# Power_Supply.net
KiCad netlist of a schematic drawn in Altium Designer
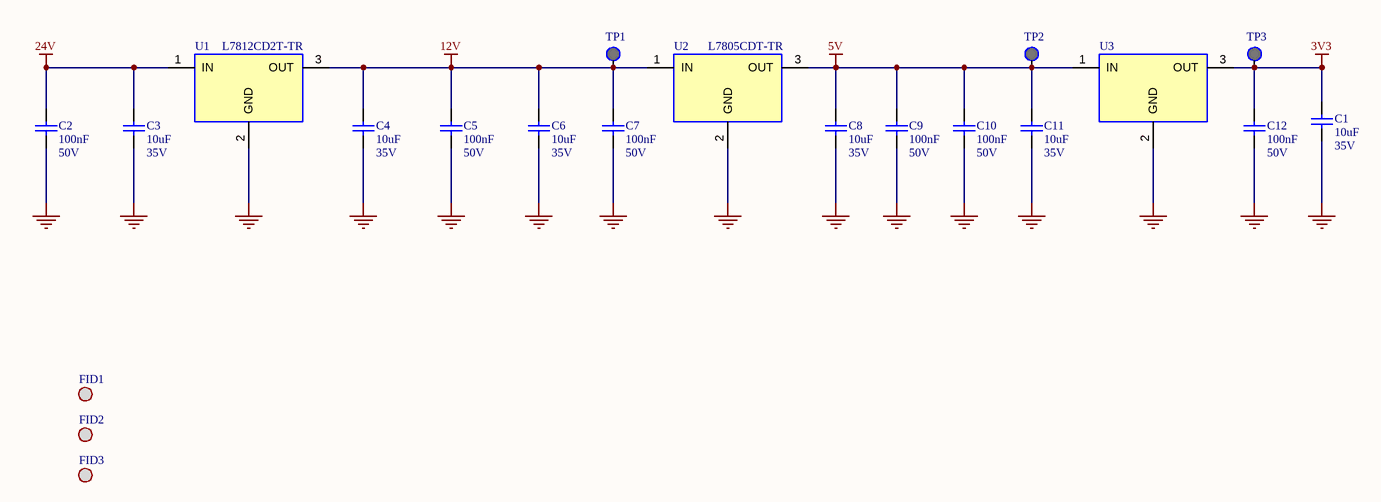
[diagram p0: Power Supply.SchDoc]

(export (version "E")
  (design (tool "Eeschema 10.0.6"))
  (components
    (comp (ref "C1")
      (value "Capacitor")
      (footprint "CAPC1608N")
      (fields
        (field (name "PART NUMBER") "CAP-000000006")
        (field (name "VALUE 1") "10uF")
        (field (name "VALUE 2") "35V")
      )
      (libsource (lib "CMA") (part "Capacitor"))
    )
    (comp (ref "C2")
      (value "Capacitor")
      (footprint "CAPC1608N")
      (fields
        (field (name "PART NUMBER") "CAP-000000002")
        (field (name "VALUE 1") "100nF")
        (field (name "VALUE 2") "50V")
      )
      (libsource (lib "CMA") (part "Capacitor"))
    )
    (comp (ref "C3")
      (value "Capacitor")
      (footprint "CAPC1608N")
      (fields
        (field (name "PART NUMBER") "CAP-000000006")
        (field (name "VALUE 1") "10uF")
        (field (name "VALUE 2") "35V")
      )
      (libsource (lib "CMA") (part "Capacitor"))
    )
    (comp (ref "C4")
      (value "Capacitor")
      (footprint "CAPC1608N")
      (fields
        (field (name "PART NUMBER") "CAP-000000006")
        (field (name "VALUE 1") "10uF")
        (field (name "VALUE 2") "35V")
      )
      (libsource (lib "CMA") (part "Capacitor"))
    )
    (comp (ref "C5")
      (value "Capacitor")
      (footprint "CAPC1608N")
      (fields
        (field (name "PART NUMBER") "CAP-000000002")
        (field (name "VALUE 1") "100nF")
        (field (name "VALUE 2") "50V")
      )
      (libsource (lib "CMA") (part "Capacitor"))
    )
    (comp (ref "C6")
      (value "Capacitor")
      (footprint "CAPC1608N")
      (fields
        (field (name "PART NUMBER") "CAP-000000006")
        (field (name "VALUE 1") "10uF")
        (field (name "VALUE 2") "35V")
      )
      (libsource (lib "CMA") (part "Capacitor"))
    )
    (comp (ref "C7")
      (value "Capacitor")
      (footprint "CAPC1608N")
      (fields
        (field (name "PART NUMBER") "CAP-000000002")
        (field (name "VALUE 1") "100nF")
        (field (name "VALUE 2") "50V")
      )
      (libsource (lib "CMA") (part "Capacitor"))
    )
    (comp (ref "C8")
      (value "Capacitor")
      (footprint "CAPC1608N")
      (fields
        (field (name "PART NUMBER") "CAP-000000006")
        (field (name "VALUE 1") "10uF")
        (field (name "VALUE 2") "35V")
      )
      (libsource (lib "CMA") (part "Capacitor"))
    )
    (comp (ref "C9")
      (value "Capacitor")
      (footprint "CAPC1608N")
      (fields
        (field (name "PART NUMBER") "CAP-000000002")
        (field (name "VALUE 1") "100nF")
        (field (name "VALUE 2") "50V")
      )
      (libsource (lib "CMA") (part "Capacitor"))
    )
    (comp (ref "C10")
      (value "Capacitor")
      (footprint "CAPC1608N")
      (fields
        (field (name "PART NUMBER") "CAP-000000002")
        (field (name "VALUE 1") "100nF")
        (field (name "VALUE 2") "50V")
      )
      (libsource (lib "CMA") (part "Capacitor"))
    )
    (comp (ref "C11")
      (value "Capacitor")
      (footprint "CAPC1608N")
      (fields
        (field (name "PART NUMBER") "CAP-000000006")
        (field (name "VALUE 1") "10uF")
        (field (name "VALUE 2") "35V")
      )
      (libsource (lib "CMA") (part "Capacitor"))
    )
    (comp (ref "C12")
      (value "Capacitor")
      (footprint "CAPC1608N")
      (fields
        (field (name "PART NUMBER") "CAP-000000002")
        (field (name "VALUE 1") "100nF")
        (field (name "VALUE 2") "50V")
      )
      (libsource (lib "CMA") (part "Capacitor"))
    )
    (comp (ref "FID1")
      (value "Fiducial")
      (footprint "FIDUCIAL-1MM")
      (fields (field (name "PART NUMBER") "MIS-000000004"))
      (libsource (lib "CMA") (part "Fiducial"))
    )
    (comp (ref "FID2")
      (value "Fiducial")
      (footprint "FIDUCIAL-1MM")
      (fields (field (name "PART NUMBER") "MIS-000000004"))
      (libsource (lib "CMA") (part "Fiducial"))
    )
    (comp (ref "FID3")
      (value "Fiducial")
      (footprint "FIDUCIAL-1MM")
      (fields (field (name "PART NUMBER") "MIS-000000004"))
      (libsource (lib "CMA") (part "Fiducial"))
    )
    (comp (ref "TP1")
      (value "Test Point")
      (footprint "TP")
      (fields (field (name "PART NUMBER") "MIS-000000003"))
      (libsource (lib "CMA") (part "TP"))
    )
    (comp (ref "TP2")
      (value "Test Point")
      (footprint "TP")
      (fields (field (name "PART NUMBER") "MIS-000000003"))
      (libsource (lib "CMA") (part "TP"))
    )
    (comp (ref "TP3")
      (value "Test Point")
      (footprint "TP")
      (fields (field (name "PART NUMBER") "MIS-000000003"))
      (libsource (lib "CMA") (part "TP"))
    )
    (comp (ref "U1")
      (value "L7812CD2T-TR")
      (footprint "D2PAK")
      (fields (field (name "PART NUMBER") "VRG-000000002"))
      (libsource (lib "CMA") (part "L7812"))
    )
    (comp (ref "U2")
      (value "L7805CDT-TR")
      (footprint "D2PAK")
      (fields (field (name "PART NUMBER") "VRG-000000001"))
      (libsource (lib "CMA") (part "L7805"))
    )
    (comp (ref "U3")
      (value "~")
      (footprint "DPAK")
      (fields (field (name "PART NUMBER") "VRG-000000003"))
      (libsource (lib "CMA") (part "LF33"))
    )
  )
  (nets
    (net (code "1") (name "3V3") (class "Default")
      (node (ref "C1") (pin "2") (pinfunction "2_2") (pintype "passive"))
      (node (ref "C12") (pin "1") (pinfunction "1_1") (pintype "passive"))
      (node (ref "TP3") (pin "1") (pinfunction "1_1") (pintype "passive"))
      (node (ref "U3") (pin "3") (pinfunction "OUT_3") (pintype "passive"))
    )
    (net (code "2") (name "5V") (class "Default")
      (node (ref "C10") (pin "1") (pinfunction "1_1") (pintype "passive"))
      (node (ref "C11") (pin "2") (pinfunction "2_2") (pintype "passive"))
      (node (ref "C8") (pin "2") (pinfunction "2_2") (pintype "passive"))
      (node (ref "C9") (pin "1") (pinfunction "1_1") (pintype "passive"))
      (node (ref "TP2") (pin "1") (pinfunction "1_1") (pintype "passive"))
      (node (ref "U2") (pin "3") (pinfunction "OUT_3") (pintype "passive"))
      (node (ref "U3") (pin "1") (pinfunction "IN_1") (pintype "passive"))
    )
    (net (code "3") (name "12V") (class "Default")
      (node (ref "C4") (pin "2") (pinfunction "2_2") (pintype "passive"))
      (node (ref "C5") (pin "1") (pinfunction "1_1") (pintype "passive"))
      (node (ref "C6") (pin "2") (pinfunction "2_2") (pintype "passive"))
      (node (ref "C7") (pin "1") (pinfunction "1_1") (pintype "passive"))
      (node (ref "TP1") (pin "1") (pinfunction "1_1") (pintype "passive"))
      (node (ref "U1") (pin "3") (pinfunction "OUT_3") (pintype "passive"))
      (node (ref "U2") (pin "1") (pinfunction "IN_1") (pintype "passive"))
    )
    (net (code "4") (name "24V") (class "Default")
      (node (ref "C2") (pin "1") (pinfunction "1_1") (pintype "passive"))
      (node (ref "C3") (pin "2") (pinfunction "2_2") (pintype "passive"))
      (node (ref "U1") (pin "1") (pinfunction "IN_1") (pintype "passive"))
    )
    (net (code "5") (name "GND") (class "Default")
      (node (ref "C1") (pin "1") (pinfunction "1_1") (pintype "passive"))
      (node (ref "C10") (pin "2") (pinfunction "2_2") (pintype "passive"))
      (node (ref "C11") (pin "1") (pinfunction "1_1") (pintype "passive"))
      (node (ref "C12") (pin "2") (pinfunction "2_2") (pintype "passive"))
      (node (ref "C2") (pin "2") (pinfunction "2_2") (pintype "passive"))
      (node (ref "C3") (pin "1") (pinfunction "1_1") (pintype "passive"))
      (node (ref "C4") (pin "1") (pinfunction "1_1") (pintype "passive"))
      (node (ref "C5") (pin "2") (pinfunction "2_2") (pintype "passive"))
      (node (ref "C6") (pin "1") (pinfunction "1_1") (pintype "passive"))
      (node (ref "C7") (pin "2") (pinfunction "2_2") (pintype "passive"))
      (node (ref "C8") (pin "1") (pinfunction "1_1") (pintype "passive"))
      (node (ref "C9") (pin "2") (pinfunction "2_2") (pintype "passive"))
      (node (ref "U1") (pin "2") (pinfunction "GND_2") (pintype "passive"))
      (node (ref "U2") (pin "2") (pinfunction "GND_2") (pintype "passive"))
      (node (ref "U3") (pin "2") (pinfunction "GND_2") (pintype "passive"))
    )
  )
)
